# Esquematico.net
KiCad netlist of a schematic drawn in Altium Designer
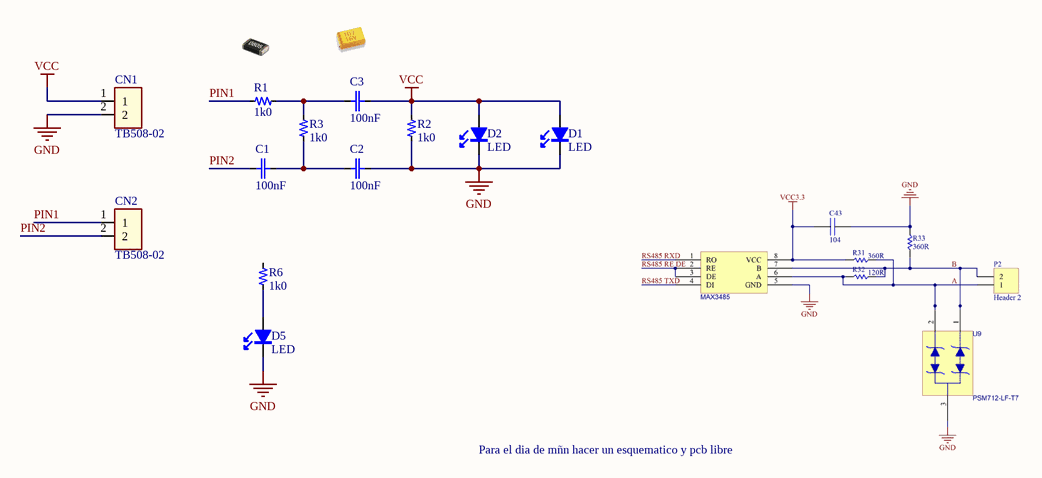
[diagram p0: Esquematico.SchDoc]

(export (version "E")
  (design (tool "Eeschema 10.0.6"))
  (components
    (comp (ref "C1")
      (value "100nF")
      (footprint "C0805")
      (description "Capacitor without polarity")
      (fields (field (name "VOLTAGE") "25V"))
      (libsource (lib "RasUNMSM") (part "Capacitor"))
    )
    (comp (ref "C2")
      (value "100nF")
      (footprint "C0805")
      (description "Capacitor without polarity")
      (fields (field (name "VOLTAGE") "25V"))
      (libsource (lib "RasUNMSM") (part "Capacitor"))
    )
    (comp (ref "C3")
      (value "100nF")
      (footprint "C0805")
      (description "Capacitor without polarity")
      (fields (field (name "VOLTAGE") "25V"))
      (libsource (lib "RasUNMSM") (part "Capacitor"))
    )
    (comp (ref "CN1")
      (value "TB508-02")
      (footprint "TB508-02")
      (description "Terminal Block")
      (libsource (lib "RasUNMSM") (part "TB-02"))
    )
    (comp (ref "CN2")
      (value "TB508-02")
      (footprint "TB508-02")
      (description "Terminal Block")
      (libsource (lib "RasUNMSM") (part "TB-02"))
    )
    (comp (ref "D1")
      (value "LED")
      (footprint "LED-0805")
      (description "LED - Light-Emitting Diode")
      (libsource (lib "RasUNMSM") (part "LED"))
    )
    (comp (ref "D2")
      (value "LED")
      (footprint "LED-0805")
      (description "LED - Light-Emitting Diode")
      (libsource (lib "RasUNMSM") (part "LED"))
    )
    (comp (ref "D5")
      (value "LED")
      (footprint "LED-1210")
      (description "LED - Light-Emitting Diode")
      (libsource (lib "RasUNMSM") (part "LED"))
    )
    (comp (ref "R1")
      (value "1k0")
      (footprint "R2512")
      (description "Single resistor")
      (fields (field (name "POWER") "0.125W"))
      (libsource (lib "RasUNMSM") (part "Resistor"))
    )
    (comp (ref "R2")
      (value "1k0")
      (footprint "R2512")
      (description "Single resistor")
      (fields (field (name "POWER") "0.125W"))
      (libsource (lib "RasUNMSM") (part "Resistor"))
    )
    (comp (ref "R3")
      (value "1k0")
      (footprint "R2512")
      (description "Single resistor")
      (fields (field (name "POWER") "0.125W"))
      (libsource (lib "RasUNMSM") (part "Resistor"))
    )
    (comp (ref "R6")
      (value "1k0")
      (footprint "R2512")
      (description "Single resistor")
      (fields (field (name "POWER") "0.125W"))
      (libsource (lib "RasUNMSM") (part "Resistor"))
    )
  )
  (nets
    (net (code "1") (name "/PIN1") (class "Default")
      (node (ref "CN2") (pin "1") (pinfunction "1_1") (pintype "passive"))
      (node (ref "R1") (pin "1") (pinfunction "1_1") (pintype "passive"))
    )
    (net (code "2") (name "/PIN2") (class "Default")
      (node (ref "C1") (pin "2") (pinfunction "2_2") (pintype "passive"))
      (node (ref "CN2") (pin "2") (pinfunction "2_2") (pintype "passive"))
    )
    (net (code "3") (name "GND") (class "Default")
      (node (ref "C2") (pin "1") (pinfunction "1_1") (pintype "passive"))
      (node (ref "CN1") (pin "2") (pinfunction "2_2") (pintype "passive"))
      (node (ref "D1") (pin "1") (pinfunction "1_1") (pintype "passive"))
      (node (ref "D2") (pin "1") (pinfunction "1_1") (pintype "passive"))
      (node (ref "D5") (pin "1") (pinfunction "1_1") (pintype "passive"))
      (node (ref "R2") (pin "1") (pinfunction "1_1") (pintype "passive"))
    )
    (net (code "4") (name "Net-(C1-Pad1)") (class "Default")
      (node (ref "C1") (pin "1") (pinfunction "1_1") (pintype "passive"))
      (node (ref "C2") (pin "2") (pinfunction "2_2") (pintype "passive"))
      (node (ref "R3") (pin "1") (pinfunction "1_1") (pintype "passive"))
    )
    (net (code "5") (name "Net-(C3-Pad2)") (class "Default")
      (node (ref "C3") (pin "2") (pinfunction "2_2") (pintype "passive"))
      (node (ref "R1") (pin "2") (pinfunction "2_2") (pintype "passive"))
      (node (ref "R3") (pin "2") (pinfunction "2_2") (pintype "passive"))
    )
    (net (code "6") (name "Net-(D5-Pad2)") (class "Default")
      (node (ref "D5") (pin "2") (pinfunction "2_2") (pintype "passive"))
      (node (ref "R6") (pin "1") (pinfunction "1_1") (pintype "passive"))
    )
    (net (code "7") (name "VCC") (class "Default")
      (node (ref "C3") (pin "1") (pinfunction "1_1") (pintype "passive"))
      (node (ref "CN1") (pin "1") (pinfunction "1_1") (pintype "passive"))
      (node (ref "D1") (pin "2") (pinfunction "2_2") (pintype "passive"))
      (node (ref "D2") (pin "2") (pinfunction "2_2") (pintype "passive"))
      (node (ref "R2") (pin "2") (pinfunction "2_2") (pintype "passive"))
    )
    (net (code "8") (name "unconnected-(R6-Pad2)") (class "Default")
      (node (ref "R6") (pin "2") (pinfunction "2_2") (pintype "passive"))
    )
  )
)
